# PPS_schematic.net
KiCad netlist of a schematic drawn in EAGLE
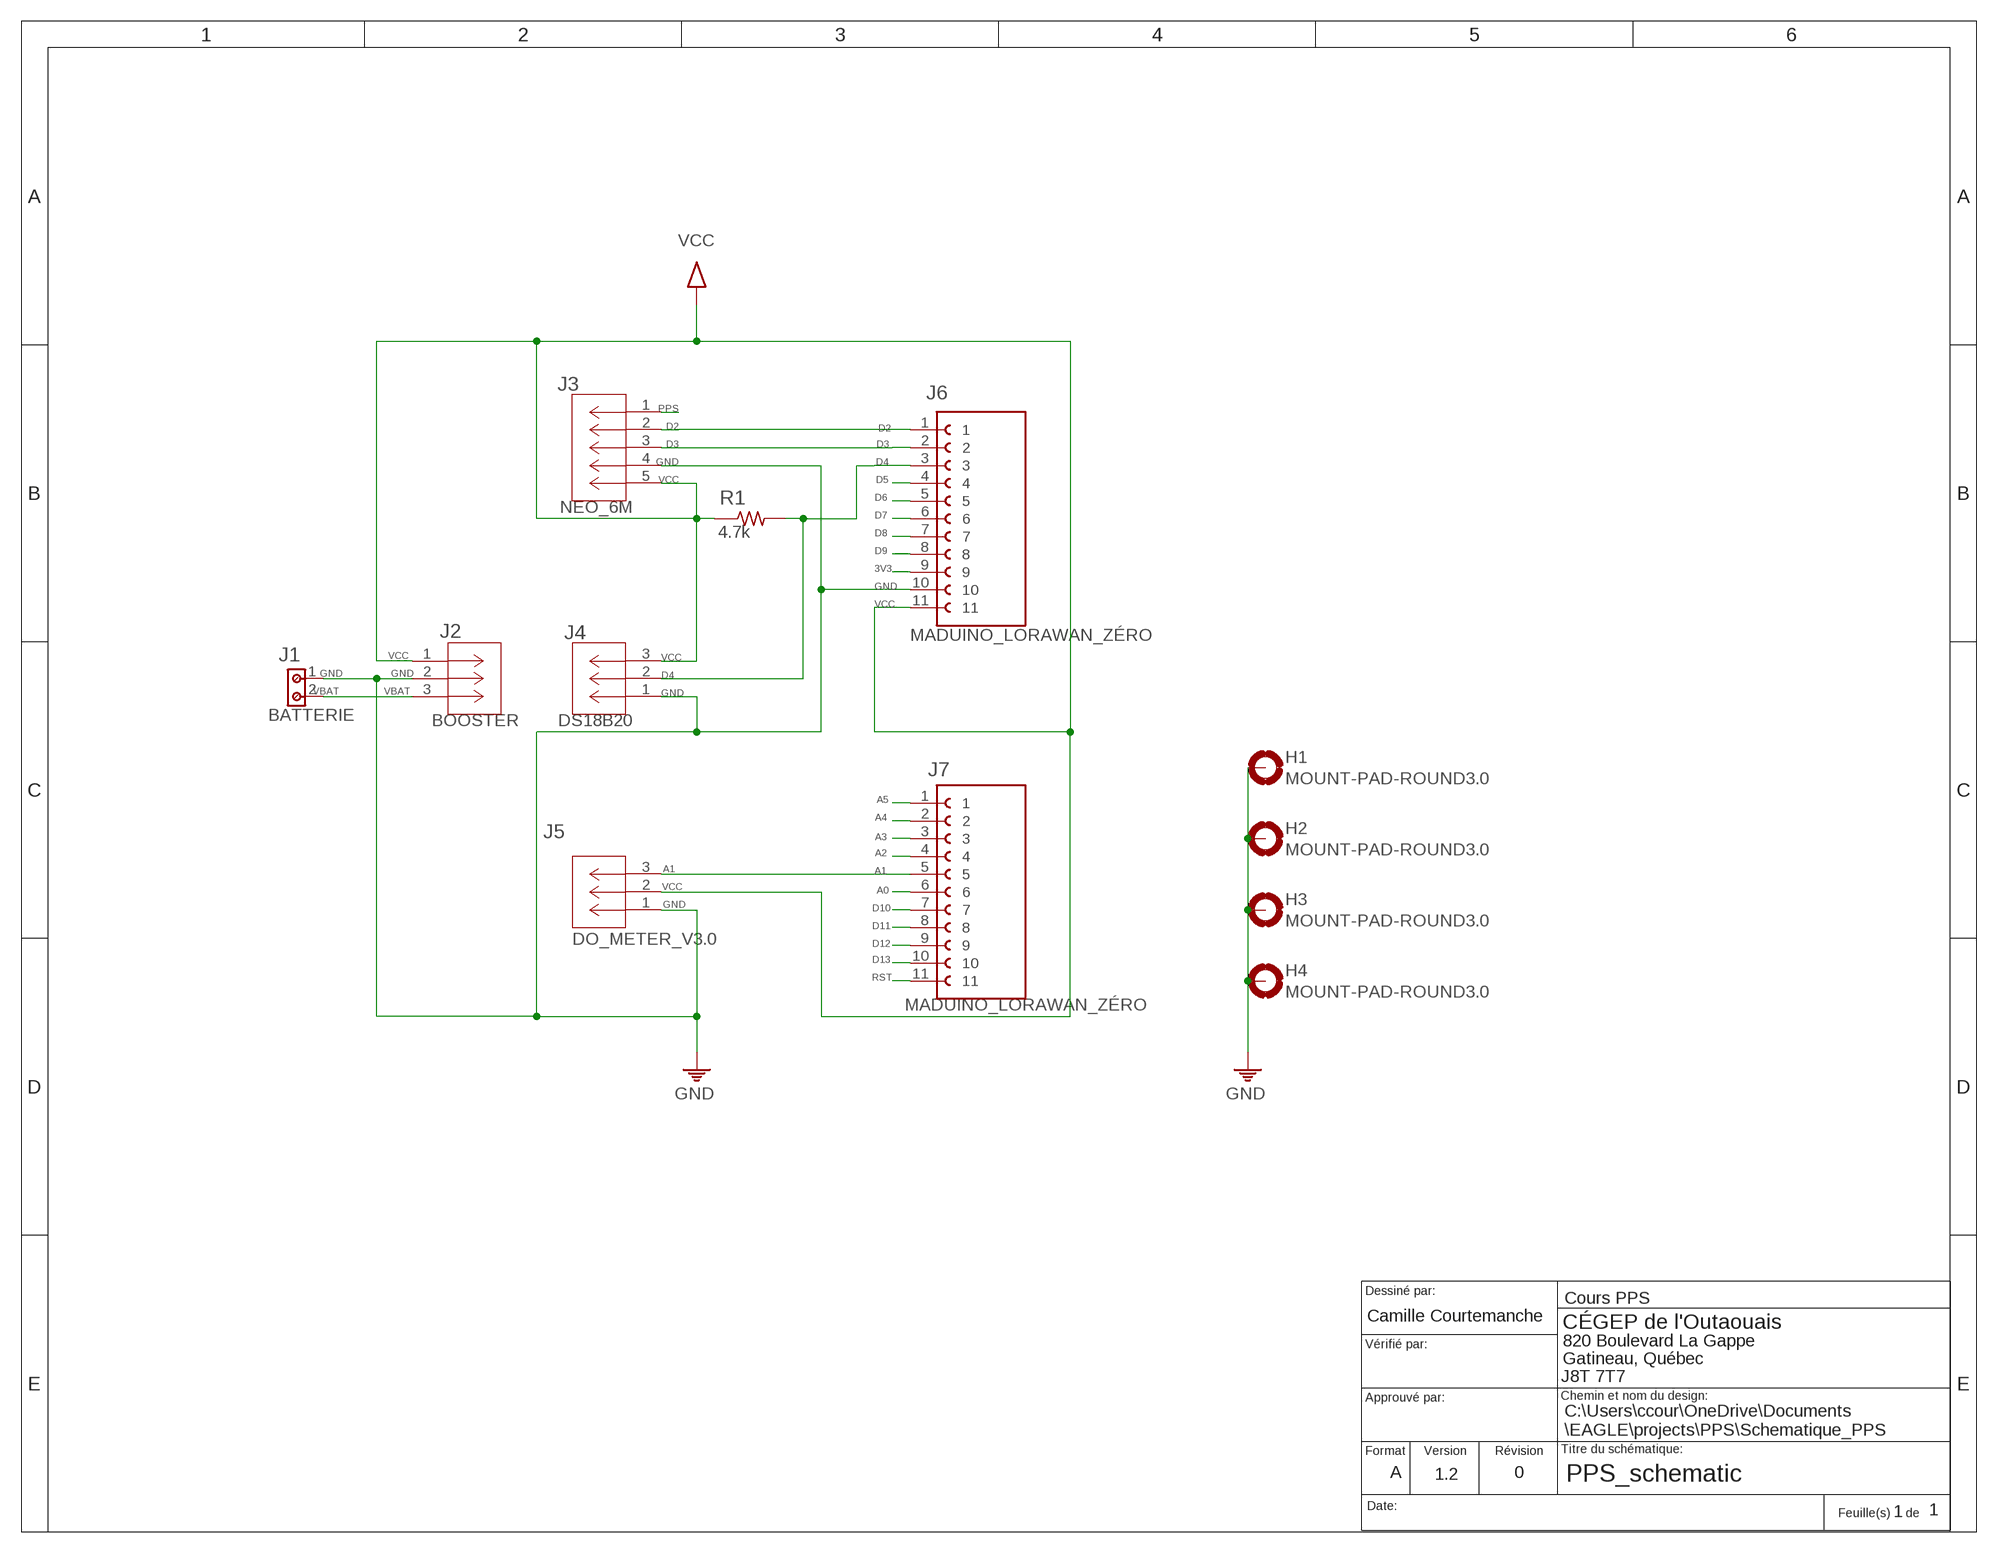
[diagram p0: schematic, sheet 1]

(export (version "E")
  (design (tool "Eeschema 10.0.6"))
  (components
    (comp (ref "H1")
      (value "MOUNT-PAD-ROUND3.0")
      (footprint "eagle-import:3,0-PAD")
      (libsource (lib "eagle-import") (part "MOUNT-PAD-ROUND3.0"))
    )
    (comp (ref "H2")
      (value "MOUNT-PAD-ROUND3.0")
      (footprint "eagle-import:3,0-PAD")
      (libsource (lib "eagle-import") (part "MOUNT-PAD-ROUND3.0"))
    )
    (comp (ref "H3")
      (value "MOUNT-PAD-ROUND3.0")
      (footprint "eagle-import:3,0-PAD")
      (libsource (lib "eagle-import") (part "MOUNT-PAD-ROUND3.0"))
    )
    (comp (ref "H4")
      (value "MOUNT-PAD-ROUND3.0")
      (footprint "eagle-import:3,0-PAD")
      (libsource (lib "eagle-import") (part "MOUNT-PAD-ROUND3.0"))
    )
    (comp (ref "J1")
      (value "Batterie")
      (footprint "eagle-import:691137710002")
      (libsource (lib "eagle-import") (part "691137710002"))
    )
    (comp (ref "J2")
      (value "BOOSTER")
      (footprint "eagle-import:CON3_1X3_TU_HTS_SAI")
      (fields
        (field (name "MANUFACTURER_PART_NUMBER") "TS-103-T-A")
        (field (name "COPYRIGHT") "Copyright (C) 2024 Ultra Librarian. All rights reserved.")
      )
      (libsource (lib "eagle-import") (part "TS-103-T-ACON3_1X3_TU_HTS_SAI"))
    )
    (comp (ref "J3")
      (value "NEO-6M")
      (footprint "eagle-import:CONN5_1LFBN-RC_SUL")
      (fields
        (field (name "MANUFACTURER_PART_NUMBER") "PPTC051LFBN-RC")
        (field (name "COPYRIGHT") "Copyright (C) 2024 Ultra Librarian. All rights reserved.")
      )
      (libsource (lib "eagle-import") (part "PPTC051LFBN-RCCONN5_1LFBN-RC_SUL"))
    )
    (comp (ref "J4")
      (value "DS18B20")
      (footprint "eagle-import:CONN_PPTC031_SUL")
      (fields
        (field (name "MANUFACTURER_PART_NUMBER") "PPTC031LFBN-RC")
        (field (name "COPYRIGHT") "Copyright (C) 2024 Ultra Librarian. All rights reserved.")
      )
      (libsource (lib "eagle-import") (part "PPTC031LFBN-RCCONN_PPTC031_SUL"))
    )
    (comp (ref "J5")
      (value "D0_METTER_v3.0")
      (footprint "eagle-import:CONN_PPTC031_SUL")
      (fields
        (field (name "MANUFACTURER_PART_NUMBER") "PPTC031LFBN-RC")
        (field (name "COPYRIGHT") "Copyright (C) 2024 Ultra Librarian. All rights reserved.")
      )
      (libsource (lib "eagle-import") (part "PPTC031LFBN-RCCONN_PPTC031_SUL"))
    )
    (comp (ref "J6")
      (value "MADUINO_LORAWAN_ZÉRO")
      (footprint "eagle-import:HARWIN_M20-7821146")
      (fields (field (name "MANUFACTURER") "HARWIN"))
      (libsource (lib "eagle-import") (part "M20-7821146"))
    )
    (comp (ref "J7")
      (value "MADUINO_LORAWAN_ZÉRO")
      (footprint "eagle-import:HARWIN_M20-7821146")
      (fields (field (name "MANUFACTURER") "HARWIN"))
      (libsource (lib "eagle-import") (part "M20-7821146"))
    )
    (comp (ref "R1")
      (value "4.7k")
      (footprint "eagle-import:M1206")
      (libsource (lib "eagle-import") (part "RM1206"))
    )
  )
  (nets
    (net (code "1") (name "/3V3") (class "Default")
      (node (ref "J6") (pin "9") (pinfunction "9_9") (pintype "passive"))
    )
    (net (code "2") (name "/A0") (class "Default")
      (node (ref "J7") (pin "6") (pinfunction "6_6") (pintype "passive"))
    )
    (net (code "3") (name "/A1") (class "Default")
      (node (ref "J5") (pin "3") (pinfunction "3_3") (pintype "passive"))
      (node (ref "J7") (pin "5") (pinfunction "5_5") (pintype "passive"))
    )
    (net (code "4") (name "/A2") (class "Default")
      (node (ref "J7") (pin "4") (pinfunction "4_4") (pintype "passive"))
    )
    (net (code "5") (name "/A3") (class "Default")
      (node (ref "J7") (pin "3") (pinfunction "3_3") (pintype "passive"))
    )
    (net (code "6") (name "/A4") (class "Default")
      (node (ref "J7") (pin "2") (pinfunction "2_2") (pintype "passive"))
    )
    (net (code "7") (name "/A5") (class "Default")
      (node (ref "J7") (pin "1") (pinfunction "1_1") (pintype "passive"))
    )
    (net (code "8") (name "/D2") (class "Default")
      (node (ref "J3") (pin "2") (pinfunction "2_2") (pintype "passive"))
      (node (ref "J6") (pin "1") (pinfunction "1_1") (pintype "passive"))
    )
    (net (code "9") (name "/D3") (class "Default")
      (node (ref "J3") (pin "3") (pinfunction "3_3") (pintype "passive"))
      (node (ref "J6") (pin "2") (pinfunction "2_2") (pintype "passive"))
    )
    (net (code "10") (name "/D4") (class "Default")
      (node (ref "J4") (pin "2") (pinfunction "2_2") (pintype "passive"))
      (node (ref "J6") (pin "3") (pinfunction "3_3") (pintype "passive"))
      (node (ref "R1") (pin "2") (pinfunction "2_2") (pintype "passive"))
    )
    (net (code "11") (name "/D5") (class "Default")
      (node (ref "J6") (pin "4") (pinfunction "4_4") (pintype "passive"))
    )
    (net (code "12") (name "/D6") (class "Default")
      (node (ref "J6") (pin "5") (pinfunction "5_5") (pintype "passive"))
    )
    (net (code "13") (name "/D7") (class "Default")
      (node (ref "J6") (pin "6") (pinfunction "6_6") (pintype "passive"))
    )
    (net (code "14") (name "/D8") (class "Default")
      (node (ref "J6") (pin "7") (pinfunction "7_7") (pintype "passive"))
    )
    (net (code "15") (name "/D9") (class "Default")
      (node (ref "J6") (pin "8") (pinfunction "8_8") (pintype "passive"))
    )
    (net (code "16") (name "/D10") (class "Default")
      (node (ref "J7") (pin "7") (pinfunction "7_7") (pintype "passive"))
    )
    (net (code "17") (name "/D11") (class "Default")
      (node (ref "J7") (pin "8") (pinfunction "8_8") (pintype "passive"))
    )
    (net (code "18") (name "/D12") (class "Default")
      (node (ref "J7") (pin "9") (pinfunction "9_9") (pintype "passive"))
    )
    (net (code "19") (name "/D13") (class "Default")
      (node (ref "J7") (pin "10") (pinfunction "10_10") (pintype "passive"))
    )
    (net (code "20") (name "/PPS") (class "Default")
      (node (ref "J3") (pin "1") (pinfunction "1_1") (pintype "passive"))
    )
    (net (code "21") (name "/RST") (class "Default")
      (node (ref "J7") (pin "11") (pinfunction "11_11") (pintype "passive"))
    )
    (net (code "22") (name "/VBAT") (class "Default")
      (node (ref "J1") (pin "2") (pinfunction "2_2") (pintype "passive"))
      (node (ref "J2") (pin "3") (pinfunction "3_3") (pintype "passive"))
    )
    (net (code "23") (name "GND") (class "Default")
      (node (ref "H1") (pin "B3,0") (pinfunction "MOUNT_B3,0") (pintype "passive"))
      (node (ref "H2") (pin "B3,0") (pinfunction "MOUNT_B3,0") (pintype "passive"))
      (node (ref "H3") (pin "B3,0") (pinfunction "MOUNT_B3,0") (pintype "passive"))
      (node (ref "H4") (pin "B3,0") (pinfunction "MOUNT_B3,0") (pintype "passive"))
      (node (ref "J1") (pin "1") (pinfunction "1_1") (pintype "passive"))
      (node (ref "J2") (pin "2") (pinfunction "2_2") (pintype "passive"))
      (node (ref "J3") (pin "4") (pinfunction "4_4") (pintype "passive"))
      (node (ref "J4") (pin "1") (pinfunction "1_1") (pintype "passive"))
      (node (ref "J5") (pin "1") (pinfunction "1_1") (pintype "passive"))
      (node (ref "J6") (pin "10") (pinfunction "10_10") (pintype "passive"))
    )
    (net (code "24") (name "VCC") (class "Default")
      (node (ref "J2") (pin "1") (pinfunction "1_1") (pintype "passive"))
      (node (ref "J3") (pin "5") (pinfunction "5_5") (pintype "passive"))
      (node (ref "J4") (pin "3") (pinfunction "3_3") (pintype "passive"))
      (node (ref "J5") (pin "2") (pinfunction "2_2") (pintype "passive"))
      (node (ref "J6") (pin "11") (pinfunction "11_11") (pintype "passive"))
      (node (ref "R1") (pin "1") (pinfunction "1_1") (pintype "passive"))
    )
  )
)
